# 07_LOAD_DestinationRegister.net
KiCad netlist of a schematic drawn in EAGLE
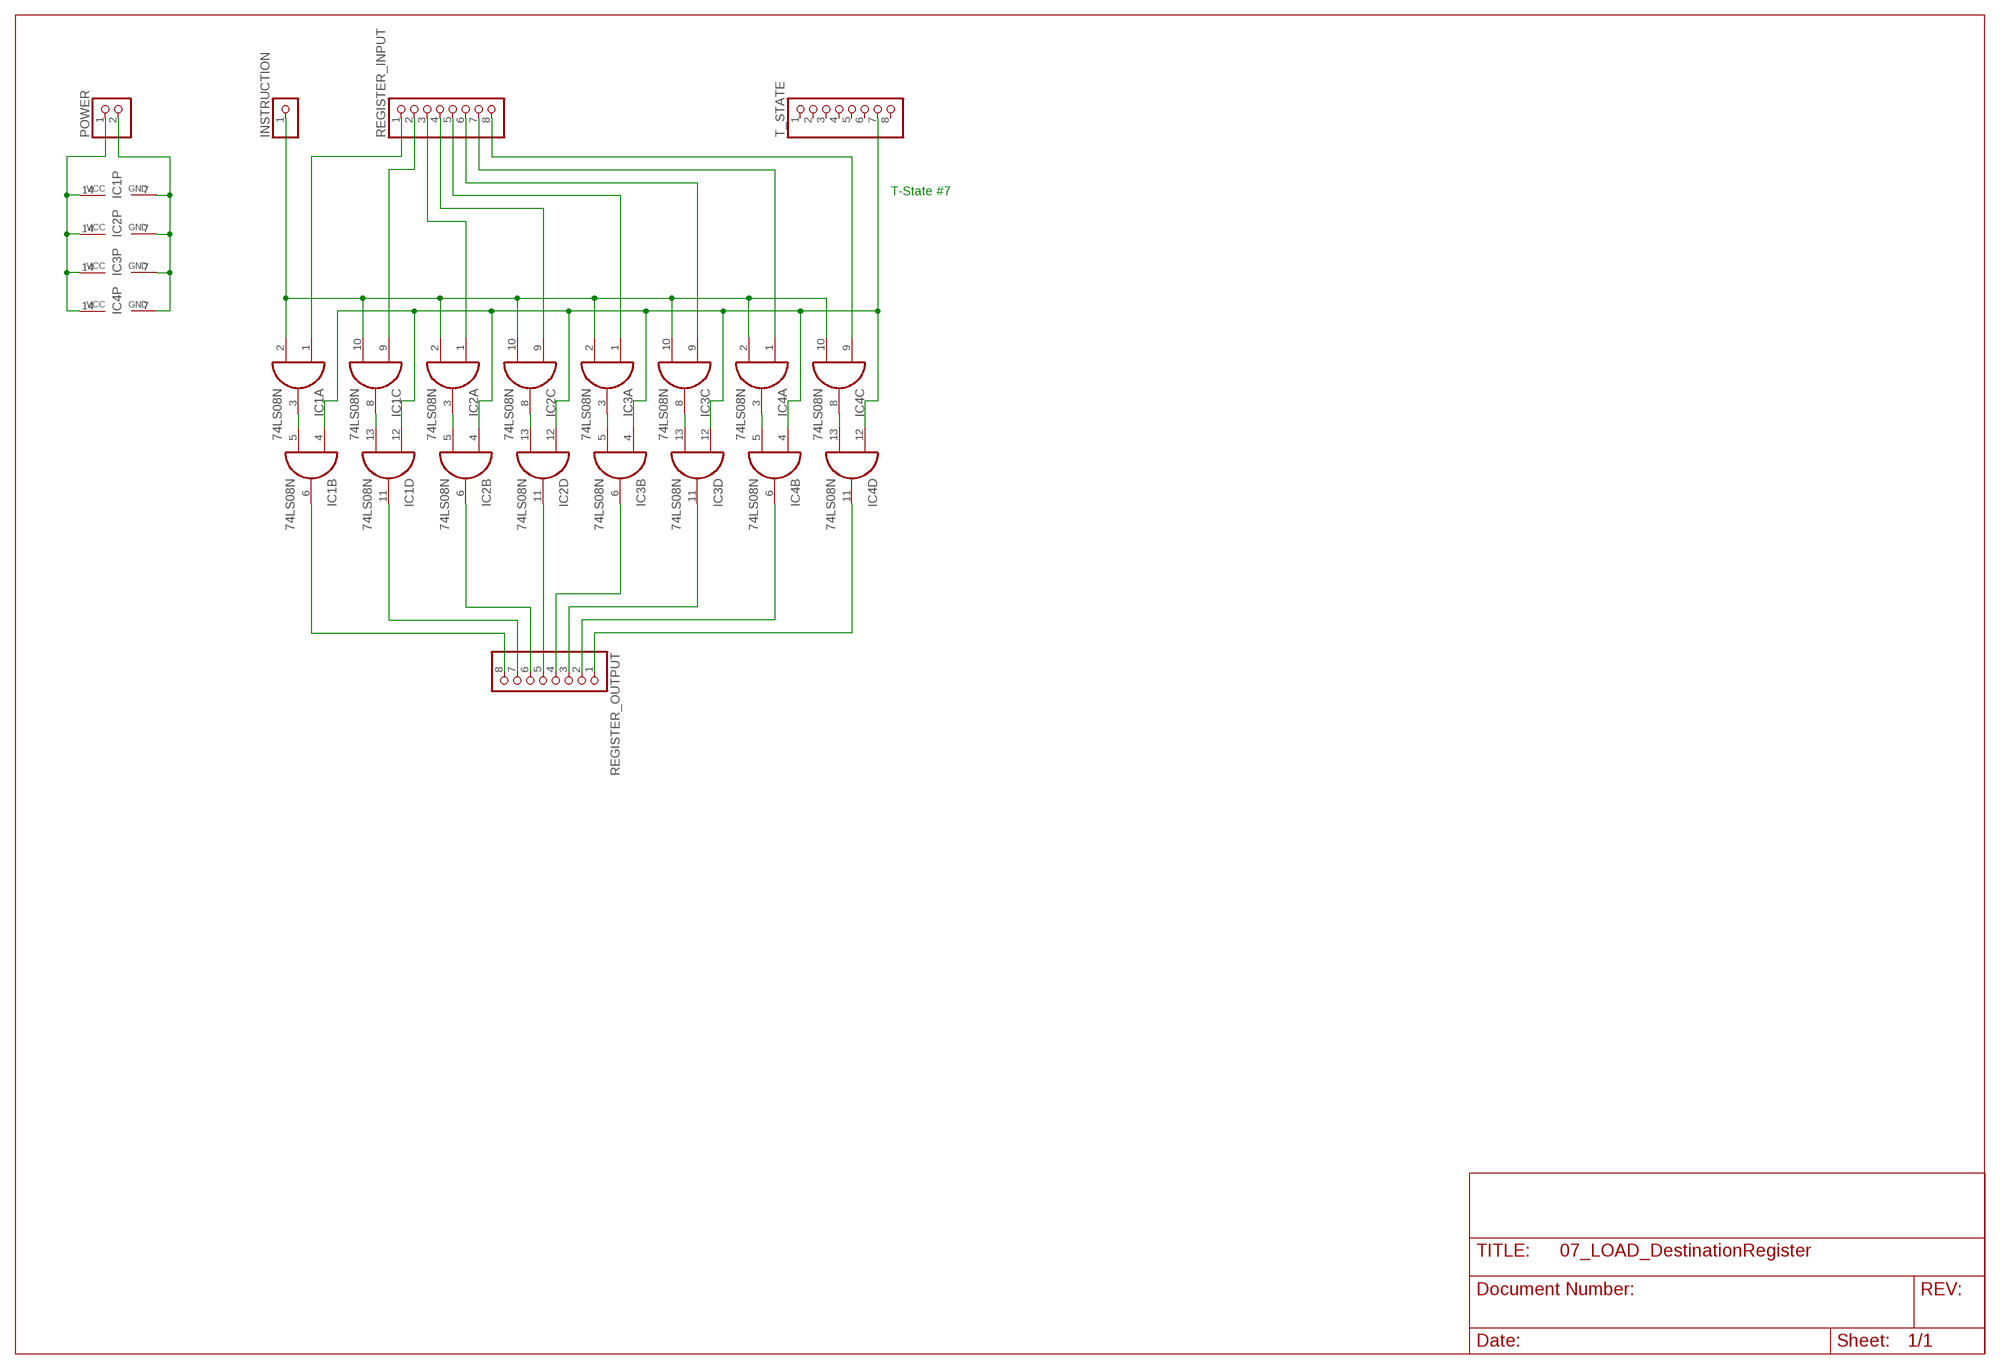
[diagram p0: schematic, sheet 1]

(export (version "E")
  (design (tool "Eeschema 10.0.6"))
  (components
    (comp (ref "IC1")
      (value "74LS08N")
      (footprint "eagle-import:DIL14")
      (libsource (lib "eagle-import") (part "7408NLS"))
    )
    (comp (ref "IC2")
      (value "74LS08N")
      (footprint "eagle-import:DIL14")
      (libsource (lib "eagle-import") (part "7408NLS"))
    )
    (comp (ref "IC3")
      (value "74LS08N")
      (footprint "eagle-import:DIL14")
      (libsource (lib "eagle-import") (part "7408NLS"))
    )
    (comp (ref "IC4")
      (value "74LS08N")
      (footprint "eagle-import:DIL14")
      (libsource (lib "eagle-import") (part "7408NLS"))
    )
    (comp (ref "INSTRUCTION")
      (value "PINHD-1X1")
      (footprint "eagle-import:1X01")
      (libsource (lib "eagle-import") (part "PINHD-1X1"))
    )
    (comp (ref "POWER")
      (value "PINHD-1X2")
      (footprint "eagle-import:1X02")
      (libsource (lib "eagle-import") (part "PINHD-1X2"))
    )
    (comp (ref "REGISTER_INPUT")
      (value "PINHD-1X8")
      (footprint "eagle-import:1X08")
      (libsource (lib "eagle-import") (part "PINHD-1X8"))
    )
    (comp (ref "REGISTER_OUTPUT")
      (value "PINHD-1X8")
      (footprint "eagle-import:1X08")
      (libsource (lib "eagle-import") (part "PINHD-1X8"))
    )
    (comp (ref "T_STATE")
      (value "PINHD-1X8")
      (footprint "eagle-import:1X08")
      (libsource (lib "eagle-import") (part "PINHD-1X8"))
    )
  )
  (nets
    (net (code "1") (name "Net-(IC1A-I0)") (class "Default")
      (node (ref "IC1") (pin "1") (pinfunction "I0_1") (pintype "input"))
      (node (ref "REGISTER_INPUT") (pin "1") (pinfunction "1_1") (pintype "passive"))
    )
    (net (code "2") (name "Net-(IC1A-I1)") (class "Default")
      (node (ref "IC1") (pin "10") (pinfunction "I1_10") (pintype "input"))
      (node (ref "IC1") (pin "2") (pinfunction "I1_2") (pintype "input"))
      (node (ref "IC2") (pin "10") (pinfunction "I1_10") (pintype "input"))
      (node (ref "IC2") (pin "2") (pinfunction "I1_2") (pintype "input"))
      (node (ref "IC3") (pin "10") (pinfunction "I1_10") (pintype "input"))
      (node (ref "IC3") (pin "2") (pinfunction "I1_2") (pintype "input"))
      (node (ref "IC4") (pin "10") (pinfunction "I1_10") (pintype "input"))
      (node (ref "IC4") (pin "2") (pinfunction "I1_2") (pintype "input"))
      (node (ref "INSTRUCTION") (pin "1") (pinfunction "1_1") (pintype "passive"))
    )
    (net (code "3") (name "Net-(IC1A-O)") (class "Default")
      (node (ref "IC1") (pin "3") (pinfunction "O_3") (pintype "output"))
      (node (ref "IC1") (pin "5") (pinfunction "I1_5") (pintype "input"))
    )
    (net (code "4") (name "Net-(IC1B-I0)") (class "Default")
      (node (ref "IC1") (pin "12") (pinfunction "I0_12") (pintype "input"))
      (node (ref "IC1") (pin "4") (pinfunction "I0_4") (pintype "input"))
      (node (ref "IC2") (pin "12") (pinfunction "I0_12") (pintype "input"))
      (node (ref "IC2") (pin "4") (pinfunction "I0_4") (pintype "input"))
      (node (ref "IC3") (pin "12") (pinfunction "I0_12") (pintype "input"))
      (node (ref "IC3") (pin "4") (pinfunction "I0_4") (pintype "input"))
      (node (ref "IC4") (pin "12") (pinfunction "I0_12") (pintype "input"))
      (node (ref "IC4") (pin "4") (pinfunction "I0_4") (pintype "input"))
      (node (ref "T_STATE") (pin "7") (pinfunction "7_7") (pintype "passive"))
    )
    (net (code "5") (name "Net-(IC1B-O)") (class "Default")
      (node (ref "IC1") (pin "6") (pinfunction "O_6") (pintype "output"))
      (node (ref "REGISTER_OUTPUT") (pin "8") (pinfunction "8_8") (pintype "passive"))
    )
    (net (code "6") (name "Net-(IC1C-I0)") (class "Default")
      (node (ref "IC1") (pin "9") (pinfunction "I0_9") (pintype "input"))
      (node (ref "REGISTER_INPUT") (pin "2") (pinfunction "2_2") (pintype "passive"))
    )
    (net (code "7") (name "Net-(IC1C-O)") (class "Default")
      (node (ref "IC1") (pin "13") (pinfunction "I1_13") (pintype "input"))
      (node (ref "IC1") (pin "8") (pinfunction "O_8") (pintype "output"))
    )
    (net (code "8") (name "Net-(IC1D-O)") (class "Default")
      (node (ref "IC1") (pin "11") (pinfunction "O_11") (pintype "output"))
      (node (ref "REGISTER_OUTPUT") (pin "7") (pinfunction "7_7") (pintype "passive"))
    )
    (net (code "9") (name "Net-(IC1E-GND)") (class "Default")
      (node (ref "IC1") (pin "7") (pinfunction "GND_7") (pintype "power_in"))
      (node (ref "IC2") (pin "7") (pinfunction "GND_7") (pintype "power_in"))
      (node (ref "IC3") (pin "7") (pinfunction "GND_7") (pintype "power_in"))
      (node (ref "IC4") (pin "7") (pinfunction "GND_7") (pintype "power_in"))
      (node (ref "POWER") (pin "2") (pinfunction "2_2") (pintype "passive"))
    )
    (net (code "10") (name "Net-(IC1E-VCC)") (class "Default")
      (node (ref "IC1") (pin "14") (pinfunction "VCC_14") (pintype "power_in"))
      (node (ref "IC2") (pin "14") (pinfunction "VCC_14") (pintype "power_in"))
      (node (ref "IC3") (pin "14") (pinfunction "VCC_14") (pintype "power_in"))
      (node (ref "IC4") (pin "14") (pinfunction "VCC_14") (pintype "power_in"))
      (node (ref "POWER") (pin "1") (pinfunction "1_1") (pintype "passive"))
    )
    (net (code "11") (name "Net-(IC2A-I0)") (class "Default")
      (node (ref "IC2") (pin "1") (pinfunction "I0_1") (pintype "input"))
      (node (ref "REGISTER_INPUT") (pin "3") (pinfunction "3_3") (pintype "passive"))
    )
    (net (code "12") (name "Net-(IC2A-O)") (class "Default")
      (node (ref "IC2") (pin "3") (pinfunction "O_3") (pintype "output"))
      (node (ref "IC2") (pin "5") (pinfunction "I1_5") (pintype "input"))
    )
    (net (code "13") (name "Net-(IC2B-O)") (class "Default")
      (node (ref "IC2") (pin "6") (pinfunction "O_6") (pintype "output"))
      (node (ref "REGISTER_OUTPUT") (pin "6") (pinfunction "6_6") (pintype "passive"))
    )
    (net (code "14") (name "Net-(IC2C-I0)") (class "Default")
      (node (ref "IC2") (pin "9") (pinfunction "I0_9") (pintype "input"))
      (node (ref "REGISTER_INPUT") (pin "4") (pinfunction "4_4") (pintype "passive"))
    )
    (net (code "15") (name "Net-(IC2C-O)") (class "Default")
      (node (ref "IC2") (pin "13") (pinfunction "I1_13") (pintype "input"))
      (node (ref "IC2") (pin "8") (pinfunction "O_8") (pintype "output"))
    )
    (net (code "16") (name "Net-(IC2D-O)") (class "Default")
      (node (ref "IC2") (pin "11") (pinfunction "O_11") (pintype "output"))
      (node (ref "REGISTER_OUTPUT") (pin "5") (pinfunction "5_5") (pintype "passive"))
    )
    (net (code "17") (name "Net-(IC3A-I0)") (class "Default")
      (node (ref "IC3") (pin "1") (pinfunction "I0_1") (pintype "input"))
      (node (ref "REGISTER_INPUT") (pin "5") (pinfunction "5_5") (pintype "passive"))
    )
    (net (code "18") (name "Net-(IC3A-O)") (class "Default")
      (node (ref "IC3") (pin "3") (pinfunction "O_3") (pintype "output"))
      (node (ref "IC3") (pin "5") (pinfunction "I1_5") (pintype "input"))
    )
    (net (code "19") (name "Net-(IC3B-O)") (class "Default")
      (node (ref "IC3") (pin "6") (pinfunction "O_6") (pintype "output"))
      (node (ref "REGISTER_OUTPUT") (pin "4") (pinfunction "4_4") (pintype "passive"))
    )
    (net (code "20") (name "Net-(IC3C-I0)") (class "Default")
      (node (ref "IC3") (pin "9") (pinfunction "I0_9") (pintype "input"))
      (node (ref "REGISTER_INPUT") (pin "6") (pinfunction "6_6") (pintype "passive"))
    )
    (net (code "21") (name "Net-(IC3C-O)") (class "Default")
      (node (ref "IC3") (pin "13") (pinfunction "I1_13") (pintype "input"))
      (node (ref "IC3") (pin "8") (pinfunction "O_8") (pintype "output"))
    )
    (net (code "22") (name "Net-(IC3D-O)") (class "Default")
      (node (ref "IC3") (pin "11") (pinfunction "O_11") (pintype "output"))
      (node (ref "REGISTER_OUTPUT") (pin "3") (pinfunction "3_3") (pintype "passive"))
    )
    (net (code "23") (name "Net-(IC4A-I0)") (class "Default")
      (node (ref "IC4") (pin "1") (pinfunction "I0_1") (pintype "input"))
      (node (ref "REGISTER_INPUT") (pin "7") (pinfunction "7_7") (pintype "passive"))
    )
    (net (code "24") (name "Net-(IC4A-O)") (class "Default")
      (node (ref "IC4") (pin "3") (pinfunction "O_3") (pintype "output"))
      (node (ref "IC4") (pin "5") (pinfunction "I1_5") (pintype "input"))
    )
    (net (code "25") (name "Net-(IC4B-O)") (class "Default")
      (node (ref "IC4") (pin "6") (pinfunction "O_6") (pintype "output"))
      (node (ref "REGISTER_OUTPUT") (pin "2") (pinfunction "2_2") (pintype "passive"))
    )
    (net (code "26") (name "Net-(IC4C-I0)") (class "Default")
      (node (ref "IC4") (pin "9") (pinfunction "I0_9") (pintype "input"))
      (node (ref "REGISTER_INPUT") (pin "8") (pinfunction "8_8") (pintype "passive"))
    )
    (net (code "27") (name "Net-(IC4C-O)") (class "Default")
      (node (ref "IC4") (pin "13") (pinfunction "I1_13") (pintype "input"))
      (node (ref "IC4") (pin "8") (pinfunction "O_8") (pintype "output"))
    )
    (net (code "28") (name "Net-(IC4D-O)") (class "Default")
      (node (ref "IC4") (pin "11") (pinfunction "O_11") (pintype "output"))
      (node (ref "REGISTER_OUTPUT") (pin "1") (pinfunction "1_1") (pintype "passive"))
    )
    (net (code "29") (name "unconnected-(T_STATE-Pad1)") (class "Default")
      (node (ref "T_STATE") (pin "1") (pinfunction "1_1") (pintype "passive"))
    )
    (net (code "30") (name "unconnected-(T_STATE-Pad2)") (class "Default")
      (node (ref "T_STATE") (pin "2") (pinfunction "2_2") (pintype "passive"))
    )
    (net (code "31") (name "unconnected-(T_STATE-Pad3)") (class "Default")
      (node (ref "T_STATE") (pin "3") (pinfunction "3_3") (pintype "passive"))
    )
    (net (code "32") (name "unconnected-(T_STATE-Pad4)") (class "Default")
      (node (ref "T_STATE") (pin "4") (pinfunction "4_4") (pintype "passive"))
    )
    (net (code "33") (name "unconnected-(T_STATE-Pad5)") (class "Default")
      (node (ref "T_STATE") (pin "5") (pinfunction "5_5") (pintype "passive"))
    )
    (net (code "34") (name "unconnected-(T_STATE-Pad6)") (class "Default")
      (node (ref "T_STATE") (pin "6") (pinfunction "6_6") (pintype "passive"))
    )
    (net (code "35") (name "unconnected-(T_STATE-Pad8)") (class "Default")
      (node (ref "T_STATE") (pin "8") (pinfunction "8_8") (pintype "passive"))
    )
  )
)
